# Bpod_RasPi_Shim_r1_1.net
KiCad netlist of a schematic drawn in EAGLE
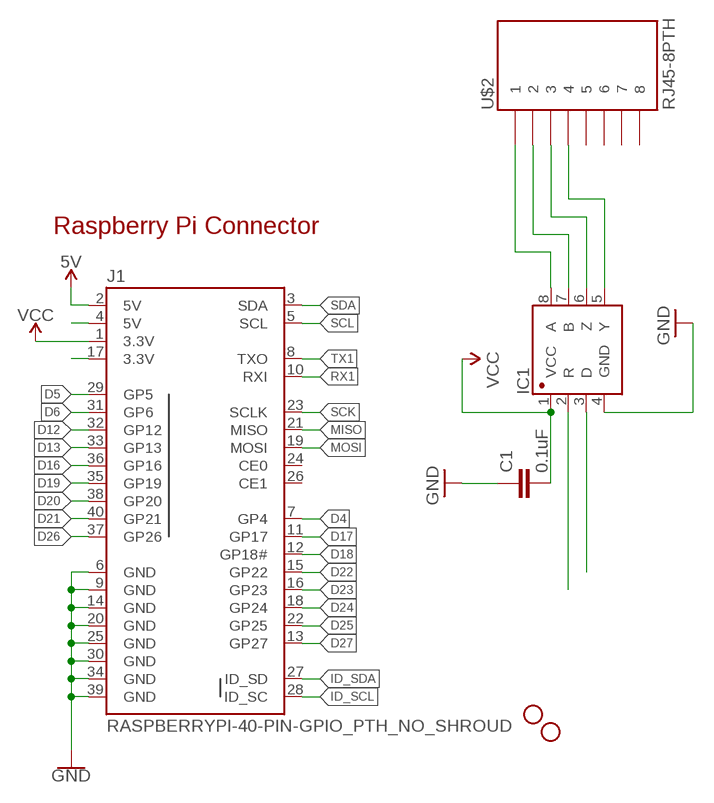
[diagram p0: schematic, sheet 1]

(export (version "E")
  (design (tool "Eeschema 10.0.6"))
  (components
    (comp (ref "C1")
      (value "0.1uF")
      (footprint "eagle-import:0805")
      (libsource (lib "eagle-import") (part "1.0UF-0805-25V-(+80/-20%)"))
    )
    (comp (ref "H3")
      (value "STAND-OFFTIGHT")
      (footprint "eagle-import:STAND-OFF-TIGHT")
      (libsource (lib "eagle-import") (part "STAND-OFFTIGHT"))
    )
    (comp (ref "H4")
      (value "STAND-OFFTIGHT")
      (footprint "eagle-import:STAND-OFF-TIGHT")
      (libsource (lib "eagle-import") (part "STAND-OFFTIGHT"))
    )
    (comp (ref "IC1")
      (value "SN65HVD31DR")
      (footprint "eagle-import:SO08")
      (libsource (lib "eagle-import") (part "SN65HVD31DR"))
    )
    (comp (ref "J1")
      (value "RASPBERRYPI-40-PIN-GPIO_PTH_NO_SHROUD")
      (footprint "eagle-import:2X20")
      (libsource (lib "eagle-import") (part "RASPBERRYPI-40-PIN-GPIO_PTH_NO_SHROUD"))
    )
    (comp (ref "U$2")
      (value "RJ45-8PTH")
      (footprint "eagle-import:RJ45-8")
      (libsource (lib "eagle-import") (part "RJ45-8PTH"))
    )
  )
  (nets
    (net (code "1") (name "5V") (class "Default")
      (node (ref "J1") (pin "2") (pinfunction "5V_2") (pintype "power_in"))
    )
    (net (code "2") (name "D4") (class "Default")
      (node (ref "J1") (pin "7") (pinfunction "GP4_7") (pintype "bidirectional"))
    )
    (net (code "3") (name "D5") (class "Default")
      (node (ref "J1") (pin "29") (pinfunction "GP5_29") (pintype "bidirectional"))
    )
    (net (code "4") (name "D6") (class "Default")
      (node (ref "J1") (pin "31") (pinfunction "GP6_31") (pintype "bidirectional"))
    )
    (net (code "5") (name "D12") (class "Default")
      (node (ref "J1") (pin "32") (pinfunction "GP12_32") (pintype "bidirectional"))
    )
    (net (code "6") (name "D13") (class "Default")
      (node (ref "J1") (pin "33") (pinfunction "GP13_33") (pintype "bidirectional"))
    )
    (net (code "7") (name "D16") (class "Default")
      (node (ref "J1") (pin "36") (pinfunction "GP16_36") (pintype "bidirectional"))
    )
    (net (code "8") (name "D17") (class "Default")
      (node (ref "J1") (pin "11") (pinfunction "GP17_11") (pintype "bidirectional"))
    )
    (net (code "9") (name "D18") (class "Default")
      (node (ref "J1") (pin "12") (pinfunction "GP18#_12") (pintype "bidirectional"))
    )
    (net (code "10") (name "D19") (class "Default")
      (node (ref "J1") (pin "35") (pinfunction "GP19_35") (pintype "bidirectional"))
    )
    (net (code "11") (name "D20") (class "Default")
      (node (ref "J1") (pin "38") (pinfunction "GP20_38") (pintype "bidirectional"))
    )
    (net (code "12") (name "D21") (class "Default")
      (node (ref "J1") (pin "40") (pinfunction "GP21_40") (pintype "bidirectional"))
    )
    (net (code "13") (name "D22") (class "Default")
      (node (ref "J1") (pin "15") (pinfunction "GP22_15") (pintype "bidirectional"))
    )
    (net (code "14") (name "D23") (class "Default")
      (node (ref "J1") (pin "16") (pinfunction "GP23_16") (pintype "bidirectional"))
    )
    (net (code "15") (name "D24") (class "Default")
      (node (ref "J1") (pin "18") (pinfunction "GP24_18") (pintype "bidirectional"))
    )
    (net (code "16") (name "D25") (class "Default")
      (node (ref "J1") (pin "22") (pinfunction "GP25_22") (pintype "bidirectional"))
    )
    (net (code "17") (name "D26") (class "Default")
      (node (ref "J1") (pin "37") (pinfunction "GP26_37") (pintype "bidirectional"))
    )
    (net (code "18") (name "D27") (class "Default")
      (node (ref "J1") (pin "13") (pinfunction "GP27_13") (pintype "bidirectional"))
    )
    (net (code "19") (name "GND") (class "Default")
      (node (ref "C1") (pin "1") (pinfunction "1_1") (pintype "passive"))
      (node (ref "IC1") (pin "4") (pinfunction "GND_4") (pintype "bidirectional"))
      (node (ref "J1") (pin "14") (pinfunction "GND_14") (pintype "power_in"))
      (node (ref "J1") (pin "20") (pinfunction "GND_20") (pintype "power_in"))
      (node (ref "J1") (pin "25") (pinfunction "GND_25") (pintype "power_in"))
      (node (ref "J1") (pin "30") (pinfunction "GND_30") (pintype "power_in"))
      (node (ref "J1") (pin "34") (pinfunction "GND_34") (pintype "power_in"))
      (node (ref "J1") (pin "39") (pinfunction "GND_39") (pintype "power_in"))
      (node (ref "J1") (pin "6") (pinfunction "GND_6") (pintype "power_in"))
      (node (ref "J1") (pin "9") (pinfunction "GND_9") (pintype "power_in"))
    )
    (net (code "20") (name "ID_SCL") (class "Default")
      (node (ref "J1") (pin "28") (pinfunction "ID_SC_28") (pintype "bidirectional"))
    )
    (net (code "21") (name "ID_SDA") (class "Default")
      (node (ref "J1") (pin "27") (pinfunction "ID_SD_27") (pintype "bidirectional"))
    )
    (net (code "22") (name "MISO") (class "Default")
      (node (ref "J1") (pin "21") (pinfunction "MISO_21") (pintype "input"))
    )
    (net (code "23") (name "MOSI") (class "Default")
      (node (ref "J1") (pin "19") (pinfunction "MOSI_19") (pintype "output"))
    )
    (net (code "24") (name "Net-(IC1-A)") (class "Default")
      (node (ref "IC1") (pin "8") (pinfunction "A_8") (pintype "bidirectional"))
      (node (ref "U$2") (pin "1") (pinfunction "1_1") (pintype "bidirectional"))
    )
    (net (code "25") (name "Net-(IC1-B)") (class "Default")
      (node (ref "IC1") (pin "7") (pinfunction "B_7") (pintype "bidirectional"))
      (node (ref "U$2") (pin "2") (pinfunction "2_2") (pintype "bidirectional"))
    )
    (net (code "26") (name "Net-(IC1-Y)") (class "Default")
      (node (ref "IC1") (pin "5") (pinfunction "Y_5") (pintype "bidirectional"))
      (node (ref "U$2") (pin "4") (pinfunction "4_4") (pintype "bidirectional"))
    )
    (net (code "27") (name "Net-(IC1-Z)") (class "Default")
      (node (ref "IC1") (pin "6") (pinfunction "Z_6") (pintype "bidirectional"))
      (node (ref "U$2") (pin "3") (pinfunction "3_3") (pintype "bidirectional"))
    )
    (net (code "28") (name "RX1") (class "Default")
      (node (ref "IC1") (pin "2") (pinfunction "R_2") (pintype "bidirectional"))
      (node (ref "J1") (pin "10") (pinfunction "RXI_10") (pintype "input"))
    )
    (net (code "29") (name "SCK") (class "Default")
      (node (ref "J1") (pin "23") (pinfunction "SCLK_23") (pintype "output"))
    )
    (net (code "30") (name "SCL") (class "Default")
      (node (ref "J1") (pin "5") (pinfunction "SCL_5") (pintype "bidirectional"))
    )
    (net (code "31") (name "SDA") (class "Default")
      (node (ref "J1") (pin "3") (pinfunction "SDA_3") (pintype "bidirectional"))
    )
    (net (code "32") (name "TX1") (class "Default")
      (node (ref "IC1") (pin "3") (pinfunction "D_3") (pintype "bidirectional"))
      (node (ref "J1") (pin "8") (pinfunction "TXO_8") (pintype "output"))
    )
    (net (code "33") (name "VCC") (class "Default")
      (node (ref "C1") (pin "2") (pinfunction "2_2") (pintype "passive"))
      (node (ref "IC1") (pin "1") (pinfunction "VCC_1") (pintype "bidirectional"))
      (node (ref "J1") (pin "1") (pinfunction "3.3V_1") (pintype "power_in"))
    )
    (net (code "34") (name "unconnected-(J1-3.3V-Pad17)") (class "Default")
      (node (ref "J1") (pin "17") (pinfunction "3.3V_17") (pintype "power_in"))
    )
    (net (code "35") (name "unconnected-(J1-5V-Pad4)") (class "Default")
      (node (ref "J1") (pin "4") (pinfunction "5V_4") (pintype "power_in"))
    )
    (net (code "36") (name "unconnected-(J1-CE0-Pad24)") (class "Default")
      (node (ref "J1") (pin "24") (pinfunction "CE0_24") (pintype "output"))
    )
    (net (code "37") (name "unconnected-(J1-CE1-Pad26)") (class "Default")
      (node (ref "J1") (pin "26") (pinfunction "CE1_26") (pintype "output"))
    )
    (net (code "38") (name "unconnected-(U$2-Pad5)") (class "Default")
      (node (ref "U$2") (pin "5") (pinfunction "5_5") (pintype "bidirectional"))
    )
    (net (code "39") (name "unconnected-(U$2-Pad6)") (class "Default")
      (node (ref "U$2") (pin "6") (pinfunction "6_6") (pintype "bidirectional"))
    )
    (net (code "40") (name "unconnected-(U$2-Pad7)") (class "Default")
      (node (ref "U$2") (pin "7") (pinfunction "7_7") (pintype "bidirectional"))
    )
    (net (code "41") (name "unconnected-(U$2-Pad8)") (class "Default")
      (node (ref "U$2") (pin "8") (pinfunction "8_8") (pintype "bidirectional"))
    )
  )
)
